# ir-blaster.net
KiCad netlist of a schematic drawn in EAGLE
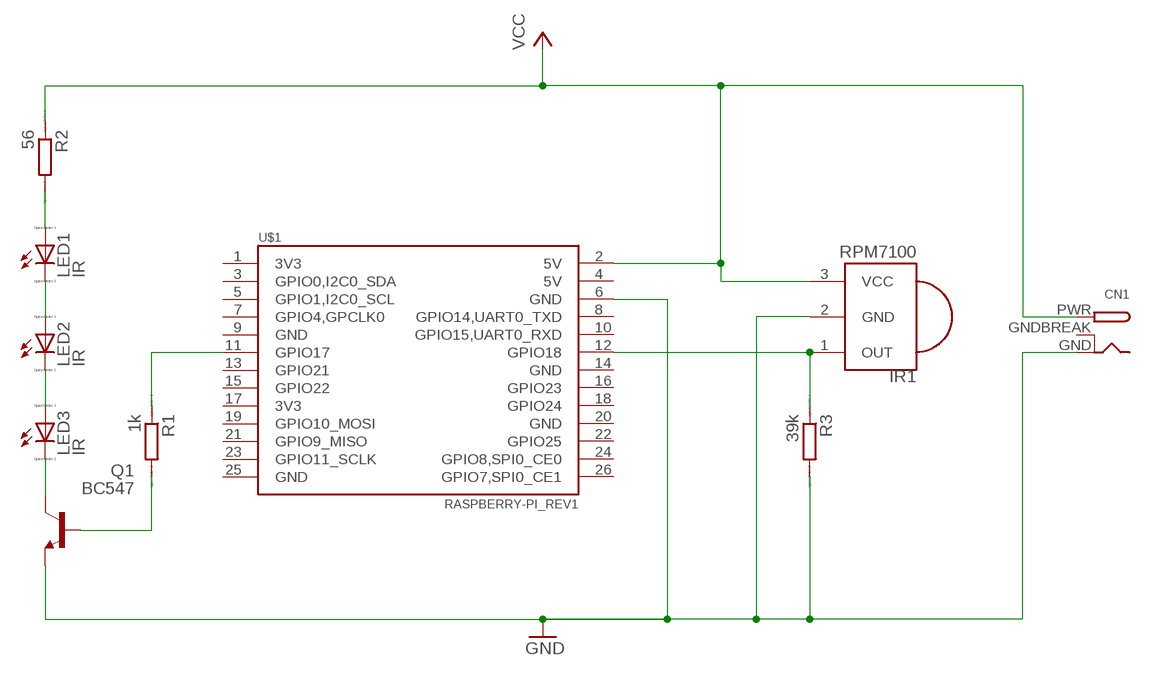
[diagram p0: schematic, sheet 1]

(export (version "E")
  (design (tool "Eeschema 10.0.6"))
  (components
    (comp (ref "CN1")
      (value "DCBARRELPTH")
      (footprint "eagle-import:DCJACK_2MM_PTH")
      (libsource (lib "eagle-import") (part "DCBARRELPTH"))
    )
    (comp (ref "IR1")
      (value "RPM7100")
      (footprint "eagle-import:PNA460XM")
      (libsource (lib "eagle-import") (part "PNA460XM"))
    )
    (comp (ref "LED1")
      (value "IR")
      (footprint "eagle-import:LED_LD260")
      (libsource (lib "eagle-import") (part "LED_ELD260"))
    )
    (comp (ref "LED2")
      (value "IR")
      (footprint "eagle-import:LED_LD260")
      (libsource (lib "eagle-import") (part "LED_ELD260"))
    )
    (comp (ref "LED3")
      (value "IR")
      (footprint "eagle-import:LED_LD260")
      (libsource (lib "eagle-import") (part "LED_ELD260"))
    )
    (comp (ref "Q1")
      (value "BC547")
      (footprint "eagle-import:TO92")
      (libsource (lib "eagle-import") (part "BC547"))
    )
    (comp (ref "R1")
      (value "1k")
      (footprint "eagle-import:0207_10")
      (libsource (lib "eagle-import") (part "R0207/10"))
    )
    (comp (ref "R2")
      (value "56")
      (footprint "eagle-import:0207_10")
      (libsource (lib "eagle-import") (part "R0207/10"))
    )
    (comp (ref "R3")
      (value "39k")
      (footprint "eagle-import:0207_10")
      (libsource (lib "eagle-import") (part "R0207/10"))
    )
    (comp (ref "U$1")
      (value "RASPBERRY-PI_REV1")
      (footprint "eagle-import:RASPBERRY-PI_REV1")
      (libsource (lib "eagle-import") (part "RASPBERRY-PI_REV1"))
    )
  )
  (nets
    (net (code "1") (name "/GNDBREAK") (class "Default")
      (node (ref "CN1") (pin "GNDBREAK") (pinfunction "GNDBREAK_GNDBREAK") (pintype "power_in"))
    )
    (net (code "2") (name "GND") (class "Default")
      (node (ref "CN1") (pin "GND") (pinfunction "GND_GND") (pintype "power_in"))
      (node (ref "IR1") (pin "2") (pinfunction "GND_2") (pintype "power_in"))
      (node (ref "Q1") (pin "1") (pinfunction "E_1") (pintype "passive"))
      (node (ref "R3") (pin "2") (pinfunction "2_2") (pintype "passive"))
      (node (ref "U$1") (pin "6") (pinfunction "GND_6") (pintype "bidirectional"))
    )
    (net (code "3") (name "Net-(IR1-OUT)") (class "Default")
      (node (ref "IR1") (pin "1") (pinfunction "OUT_1") (pintype "output"))
      (node (ref "R3") (pin "1") (pinfunction "1_1") (pintype "passive"))
      (node (ref "U$1") (pin "12") (pinfunction "GPIO18_12") (pintype "bidirectional"))
    )
    (net (code "4") (name "Net-(LED1-C)") (class "Default")
      (node (ref "LED1") (pin "K") (pinfunction "C_K") (pintype "passive"))
      (node (ref "LED2") (pin "A") (pinfunction "A_A") (pintype "passive"))
    )
    (net (code "5") (name "Net-(LED1-PadA)") (class "Default")
      (node (ref "LED1") (pin "A") (pinfunction "A_A") (pintype "passive"))
      (node (ref "R2") (pin "2") (pinfunction "2_2") (pintype "passive"))
    )
    (net (code "6") (name "Net-(LED2-C)") (class "Default")
      (node (ref "LED2") (pin "K") (pinfunction "C_K") (pintype "passive"))
      (node (ref "LED3") (pin "A") (pinfunction "A_A") (pintype "passive"))
    )
    (net (code "7") (name "Net-(LED3-C)") (class "Default")
      (node (ref "LED3") (pin "K") (pinfunction "C_K") (pintype "passive"))
      (node (ref "Q1") (pin "3") (pinfunction "C_3") (pintype "passive"))
    )
    (net (code "8") (name "Net-(Q1-B)") (class "Default")
      (node (ref "Q1") (pin "2") (pinfunction "B_2") (pintype "passive"))
      (node (ref "R1") (pin "2") (pinfunction "2_2") (pintype "passive"))
    )
    (net (code "9") (name "Net-(U$1-GPIO17)") (class "Default")
      (node (ref "R1") (pin "1") (pinfunction "1_1") (pintype "passive"))
      (node (ref "U$1") (pin "11") (pinfunction "GPIO17_11") (pintype "bidirectional"))
    )
    (net (code "10") (name "VCC") (class "Default")
      (node (ref "CN1") (pin "PWR") (pinfunction "PWR_PWR") (pintype "power_in"))
      (node (ref "IR1") (pin "3") (pinfunction "VCC_3") (pintype "power_in"))
      (node (ref "R2") (pin "1") (pinfunction "1_1") (pintype "passive"))
      (node (ref "U$1") (pin "2") (pinfunction "5V_2") (pintype "bidirectional"))
    )
    (net (code "11") (name "unconnected-(U$1-3V3-Pad1)") (class "Default")
      (node (ref "U$1") (pin "1") (pinfunction "3V3_1") (pintype "bidirectional"))
    )
    (net (code "12") (name "unconnected-(U$1-3V3-Pad17)") (class "Default")
      (node (ref "U$1") (pin "17") (pinfunction "3V3_17") (pintype "bidirectional"))
    )
    (net (code "13") (name "unconnected-(U$1-5V-Pad4)") (class "Default")
      (node (ref "U$1") (pin "4") (pinfunction "5V_4") (pintype "bidirectional"))
    )
    (net (code "14") (name "unconnected-(U$1-GND-Pad9)") (class "Default")
      (node (ref "U$1") (pin "9") (pinfunction "GND_9") (pintype "bidirectional"))
    )
    (net (code "15") (name "unconnected-(U$1-GND-Pad14)") (class "Default")
      (node (ref "U$1") (pin "14") (pinfunction "GND_14") (pintype "bidirectional"))
    )
    (net (code "16") (name "unconnected-(U$1-GND-Pad20)") (class "Default")
      (node (ref "U$1") (pin "20") (pinfunction "GND_20") (pintype "bidirectional"))
    )
    (net (code "17") (name "unconnected-(U$1-GND-Pad25)") (class "Default")
      (node (ref "U$1") (pin "25") (pinfunction "GND_25") (pintype "bidirectional"))
    )
    (net (code "18") (name "unconnected-(U$1-GPIO0,I2C0_SDA-Pad3)") (class "Default")
      (node (ref "U$1") (pin "3") (pinfunction "GPIO0,I2C0_SDA_3") (pintype "bidirectional"))
    )
    (net (code "19") (name "unconnected-(U$1-GPIO1,I2C0_SCL-Pad5)") (class "Default")
      (node (ref "U$1") (pin "5") (pinfunction "GPIO1,I2C0_SCL_5") (pintype "bidirectional"))
    )
    (net (code "20") (name "unconnected-(U$1-GPIO4,GPCLK0-Pad7)") (class "Default")
      (node (ref "U$1") (pin "7") (pinfunction "GPIO4,GPCLK0_7") (pintype "bidirectional"))
    )
    (net (code "21") (name "unconnected-(U$1-GPIO7,SPI0_CE1-Pad26)") (class "Default")
      (node (ref "U$1") (pin "26") (pinfunction "GPIO7,SPI0_CE1_26") (pintype "bidirectional"))
    )
    (net (code "22") (name "unconnected-(U$1-GPIO8,SPI0_CE0-Pad24)") (class "Default")
      (node (ref "U$1") (pin "24") (pinfunction "GPIO8,SPI0_CE0_24") (pintype "bidirectional"))
    )
    (net (code "23") (name "unconnected-(U$1-GPIO9_MISO-Pad21)") (class "Default")
      (node (ref "U$1") (pin "21") (pinfunction "GPIO9_MISO_21") (pintype "bidirectional"))
    )
    (net (code "24") (name "unconnected-(U$1-GPIO10_MOSI-Pad19)") (class "Default")
      (node (ref "U$1") (pin "19") (pinfunction "GPIO10_MOSI_19") (pintype "bidirectional"))
    )
    (net (code "25") (name "unconnected-(U$1-GPIO11_SCLK-Pad23)") (class "Default")
      (node (ref "U$1") (pin "23") (pinfunction "GPIO11_SCLK_23") (pintype "bidirectional"))
    )
    (net (code "26") (name "unconnected-(U$1-GPIO14,UART0_TXD-Pad8)") (class "Default")
      (node (ref "U$1") (pin "8") (pinfunction "GPIO14,UART0_TXD_8") (pintype "bidirectional"))
    )
    (net (code "27") (name "unconnected-(U$1-GPIO15,UART0_RXD-Pad10)") (class "Default")
      (node (ref "U$1") (pin "10") (pinfunction "GPIO15,UART0_RXD_10") (pintype "bidirectional"))
    )
    (net (code "28") (name "unconnected-(U$1-GPIO21-Pad13)") (class "Default")
      (node (ref "U$1") (pin "13") (pinfunction "GPIO21_13") (pintype "bidirectional"))
    )
    (net (code "29") (name "unconnected-(U$1-GPIO22-Pad15)") (class "Default")
      (node (ref "U$1") (pin "15") (pinfunction "GPIO22_15") (pintype "bidirectional"))
    )
    (net (code "30") (name "unconnected-(U$1-GPIO23-Pad16)") (class "Default")
      (node (ref "U$1") (pin "16") (pinfunction "GPIO23_16") (pintype "bidirectional"))
    )
    (net (code "31") (name "unconnected-(U$1-GPIO24-Pad18)") (class "Default")
      (node (ref "U$1") (pin "18") (pinfunction "GPIO24_18") (pintype "bidirectional"))
    )
    (net (code "32") (name "unconnected-(U$1-GPIO25-Pad22)") (class "Default")
      (node (ref "U$1") (pin "22") (pinfunction "GPIO25_22") (pintype "bidirectional"))
    )
  )
)
